# power.net
KiCad netlist of a schematic drawn in Altium Designer
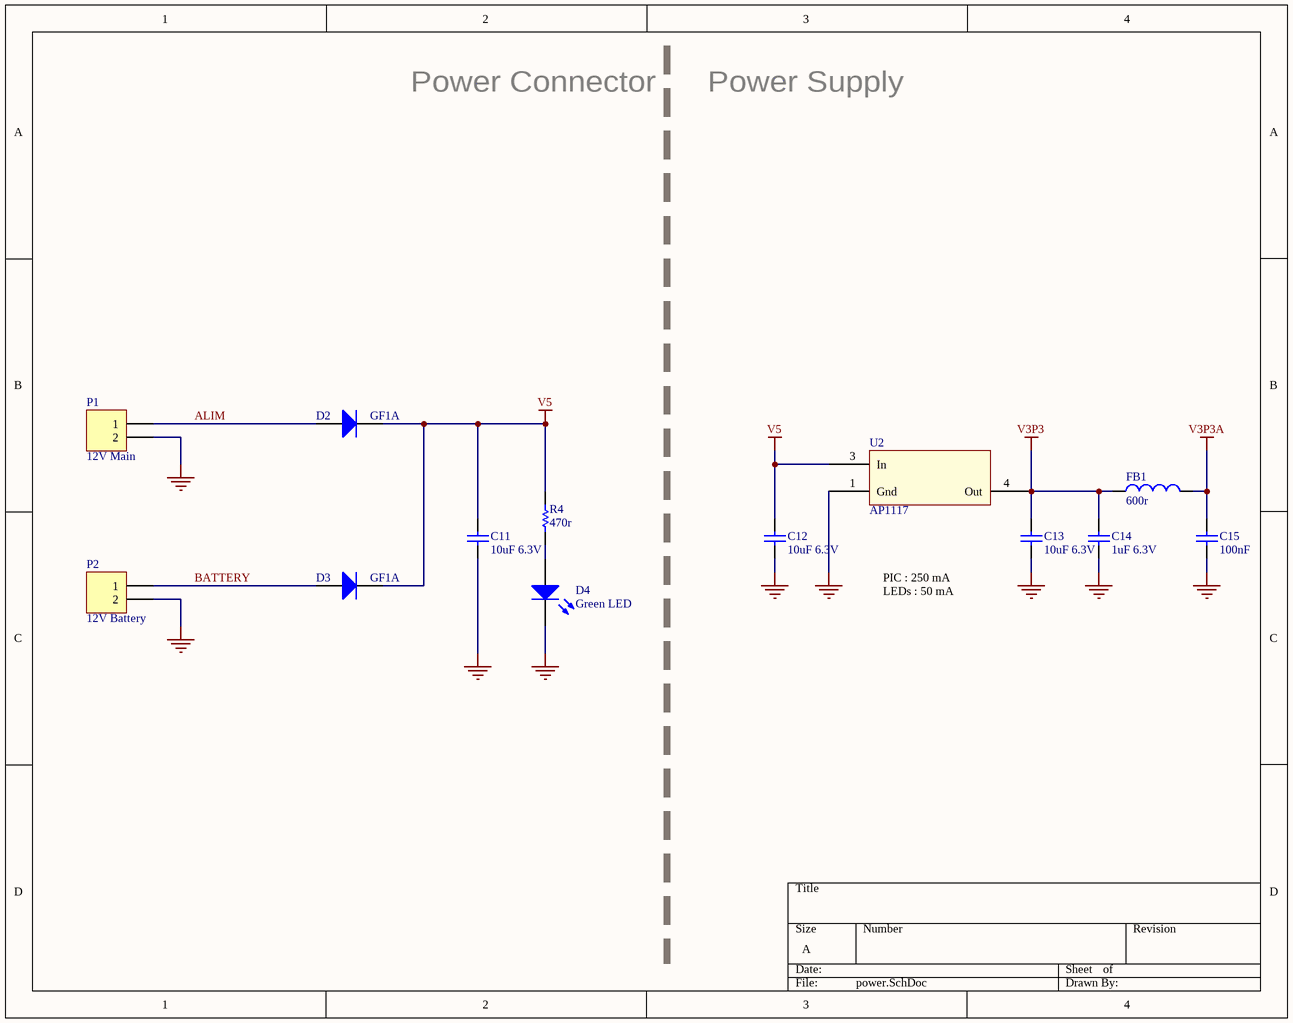
[diagram p0: power.SchDoc]

(export (version "E")
  (design (tool "Eeschema 10.0.6"))
  (components
    (comp (ref "C11")
      (value "10uF 6.3V")
      (footprint "CAPC2012N")
      (description "Capacitor")
      (fields (field (name "PUBLISHER") "Altium Limited"))
      (libsource (lib "Miscellaneous Devices") (part "Cap"))
    )
    (comp (ref "C12")
      (value "10uF 6.3V")
      (footprint "CAPC2012N")
      (description "Capacitor")
      (fields (field (name "PUBLISHER") "Altium Limited"))
      (libsource (lib "Miscellaneous Devices") (part "Cap"))
    )
    (comp (ref "C13")
      (value "10uF 6.3V")
      (footprint "CAPC2012N")
      (description "Capacitor")
      (fields (field (name "PUBLISHER") "Altium Limited"))
      (libsource (lib "Miscellaneous Devices") (part "Cap"))
    )
    (comp (ref "C14")
      (value "1uF 6.3V")
      (footprint "CAPC1608N")
      (description "Capacitor")
      (fields (field (name "PUBLISHER") "Altium Limited"))
      (libsource (lib "Miscellaneous Devices") (part "Cap"))
    )
    (comp (ref "C15")
      (value "100nF")
      (footprint "CAPC1608N")
      (description "Capacitor")
      (fields (field (name "PUBLISHER") "Altium Limited"))
      (libsource (lib "Miscellaneous Devices") (part "Cap"))
    )
    (comp (ref "D2")
      (value "GF1A")
      (footprint "SMA/DO-214AC_21")
      (description "Default Diode")
      (fields (field (name "PUBLISHER") "Altium Limited"))
      (libsource (lib "Miscellaneous Devices") (part "Diode"))
    )
    (comp (ref "D3")
      (value "GF1A")
      (footprint "SMA/DO-214AC_21")
      (description "Default Diode")
      (fields (field (name "PUBLISHER") "Altium Limited"))
      (libsource (lib "Miscellaneous Devices") (part "Diode"))
    )
    (comp (ref "D4")
      (value "Green LED")
      (footprint "LED 0805")
      (description "Typical INFRARED GaAs LED")
      (fields (field (name "PUBLISHER") "Altium Limited"))
      (libsource (lib "Miscellaneous Devices") (part "LED0"))
    )
    (comp (ref "FB1")
      (value "600r")
      (footprint "INDC1608AN")
      (description "Inductor")
      (fields (field (name "PUBLISHER") "Altium Limited"))
      (libsource (lib "Miscellaneous Devices") (part "Inductor"))
    )
    (comp (ref "P1")
      (value "12V Main")
      (footprint "PHOENIX_1985195")
      (description "Header, 2-Pin")
      (fields (field (name "PUBLISHER") "Altium Limited"))
      (libsource (lib "Miscellaneous Connectors") (part "Header 2"))
    )
    (comp (ref "P2")
      (value "12V Battery")
      (footprint "PHOENIX_1985195")
      (description "Header, 2-Pin")
      (fields (field (name "PUBLISHER") "Altium Limited"))
      (libsource (lib "Miscellaneous Connectors") (part "Header 2"))
    )
    (comp (ref "R4")
      (value "470r")
      (footprint "RESC1608N")
      (description "Resistor")
      (fields (field (name "PUBLISHER") "Altium Limited"))
      (libsource (lib "Miscellaneous Devices") (part "Res1"))
    )
    (comp (ref "U2")
      (value "AP1117")
      (footprint "TD03B_N")
      (description "1A LDO, 18V input, DPAK")
      (libsource (lib "TP2") (part "AP1117"))
    )
  )
  (nets
    (net (code "1") (name "/ALIM") (class "Default")
      (node (ref "D2") (pin "1") (pinfunction "A_1") (pintype "passive"))
      (node (ref "P1") (pin "1") (pinfunction "1_1") (pintype "passive"))
    )
    (net (code "2") (name "/BATTERY") (class "Default")
      (node (ref "D3") (pin "1") (pinfunction "A_1") (pintype "passive"))
      (node (ref "P2") (pin "1") (pinfunction "1_1") (pintype "passive"))
    )
    (net (code "3") (name "GND") (class "Default")
      (node (ref "C11") (pin "1") (pinfunction "1_1") (pintype "passive"))
      (node (ref "C12") (pin "2") (pinfunction "2_2") (pintype "passive"))
      (node (ref "C13") (pin "2") (pinfunction "2_2") (pintype "passive"))
      (node (ref "C14") (pin "1") (pinfunction "1_1") (pintype "passive"))
      (node (ref "C15") (pin "1") (pinfunction "1_1") (pintype "passive"))
      (node (ref "D4") (pin "2") (pinfunction "K_2") (pintype "passive"))
      (node (ref "P1") (pin "2") (pinfunction "2_2") (pintype "passive"))
      (node (ref "P2") (pin "2") (pinfunction "2_2") (pintype "passive"))
      (node (ref "U2") (pin "1") (pinfunction "Gnd_1") (pintype "power_in"))
    )
    (net (code "4") (name "Net-(D4-A)") (class "Default")
      (node (ref "D4") (pin "1") (pinfunction "A_1") (pintype "passive"))
      (node (ref "R4") (pin "1") (pinfunction "1_1") (pintype "passive"))
    )
    (net (code "5") (name "V3P3") (class "Default")
      (node (ref "C13") (pin "1") (pinfunction "1_1") (pintype "passive"))
      (node (ref "C14") (pin "2") (pinfunction "2_2") (pintype "passive"))
      (node (ref "FB1") (pin "1") (pinfunction "1_1") (pintype "passive"))
      (node (ref "U2") (pin "4") (pinfunction "Out_4") (pintype "power_in"))
    )
    (net (code "6") (name "V3P3A") (class "Default")
      (node (ref "C15") (pin "2") (pinfunction "2_2") (pintype "passive"))
      (node (ref "FB1") (pin "2") (pinfunction "2_2") (pintype "passive"))
    )
    (net (code "7") (name "V5") (class "Default")
      (node (ref "C11") (pin "2") (pinfunction "2_2") (pintype "passive"))
      (node (ref "C12") (pin "1") (pinfunction "1_1") (pintype "passive"))
      (node (ref "D2") (pin "2") (pinfunction "K_2") (pintype "passive"))
      (node (ref "D3") (pin "2") (pinfunction "K_2") (pintype "passive"))
      (node (ref "R4") (pin "2") (pinfunction "2_2") (pintype "passive"))
      (node (ref "U2") (pin "3") (pinfunction "In_3") (pintype "power_in"))
    )
  )
)
